# design.net
KiCad netlist of a schematic drawn in EasyEDA Pro
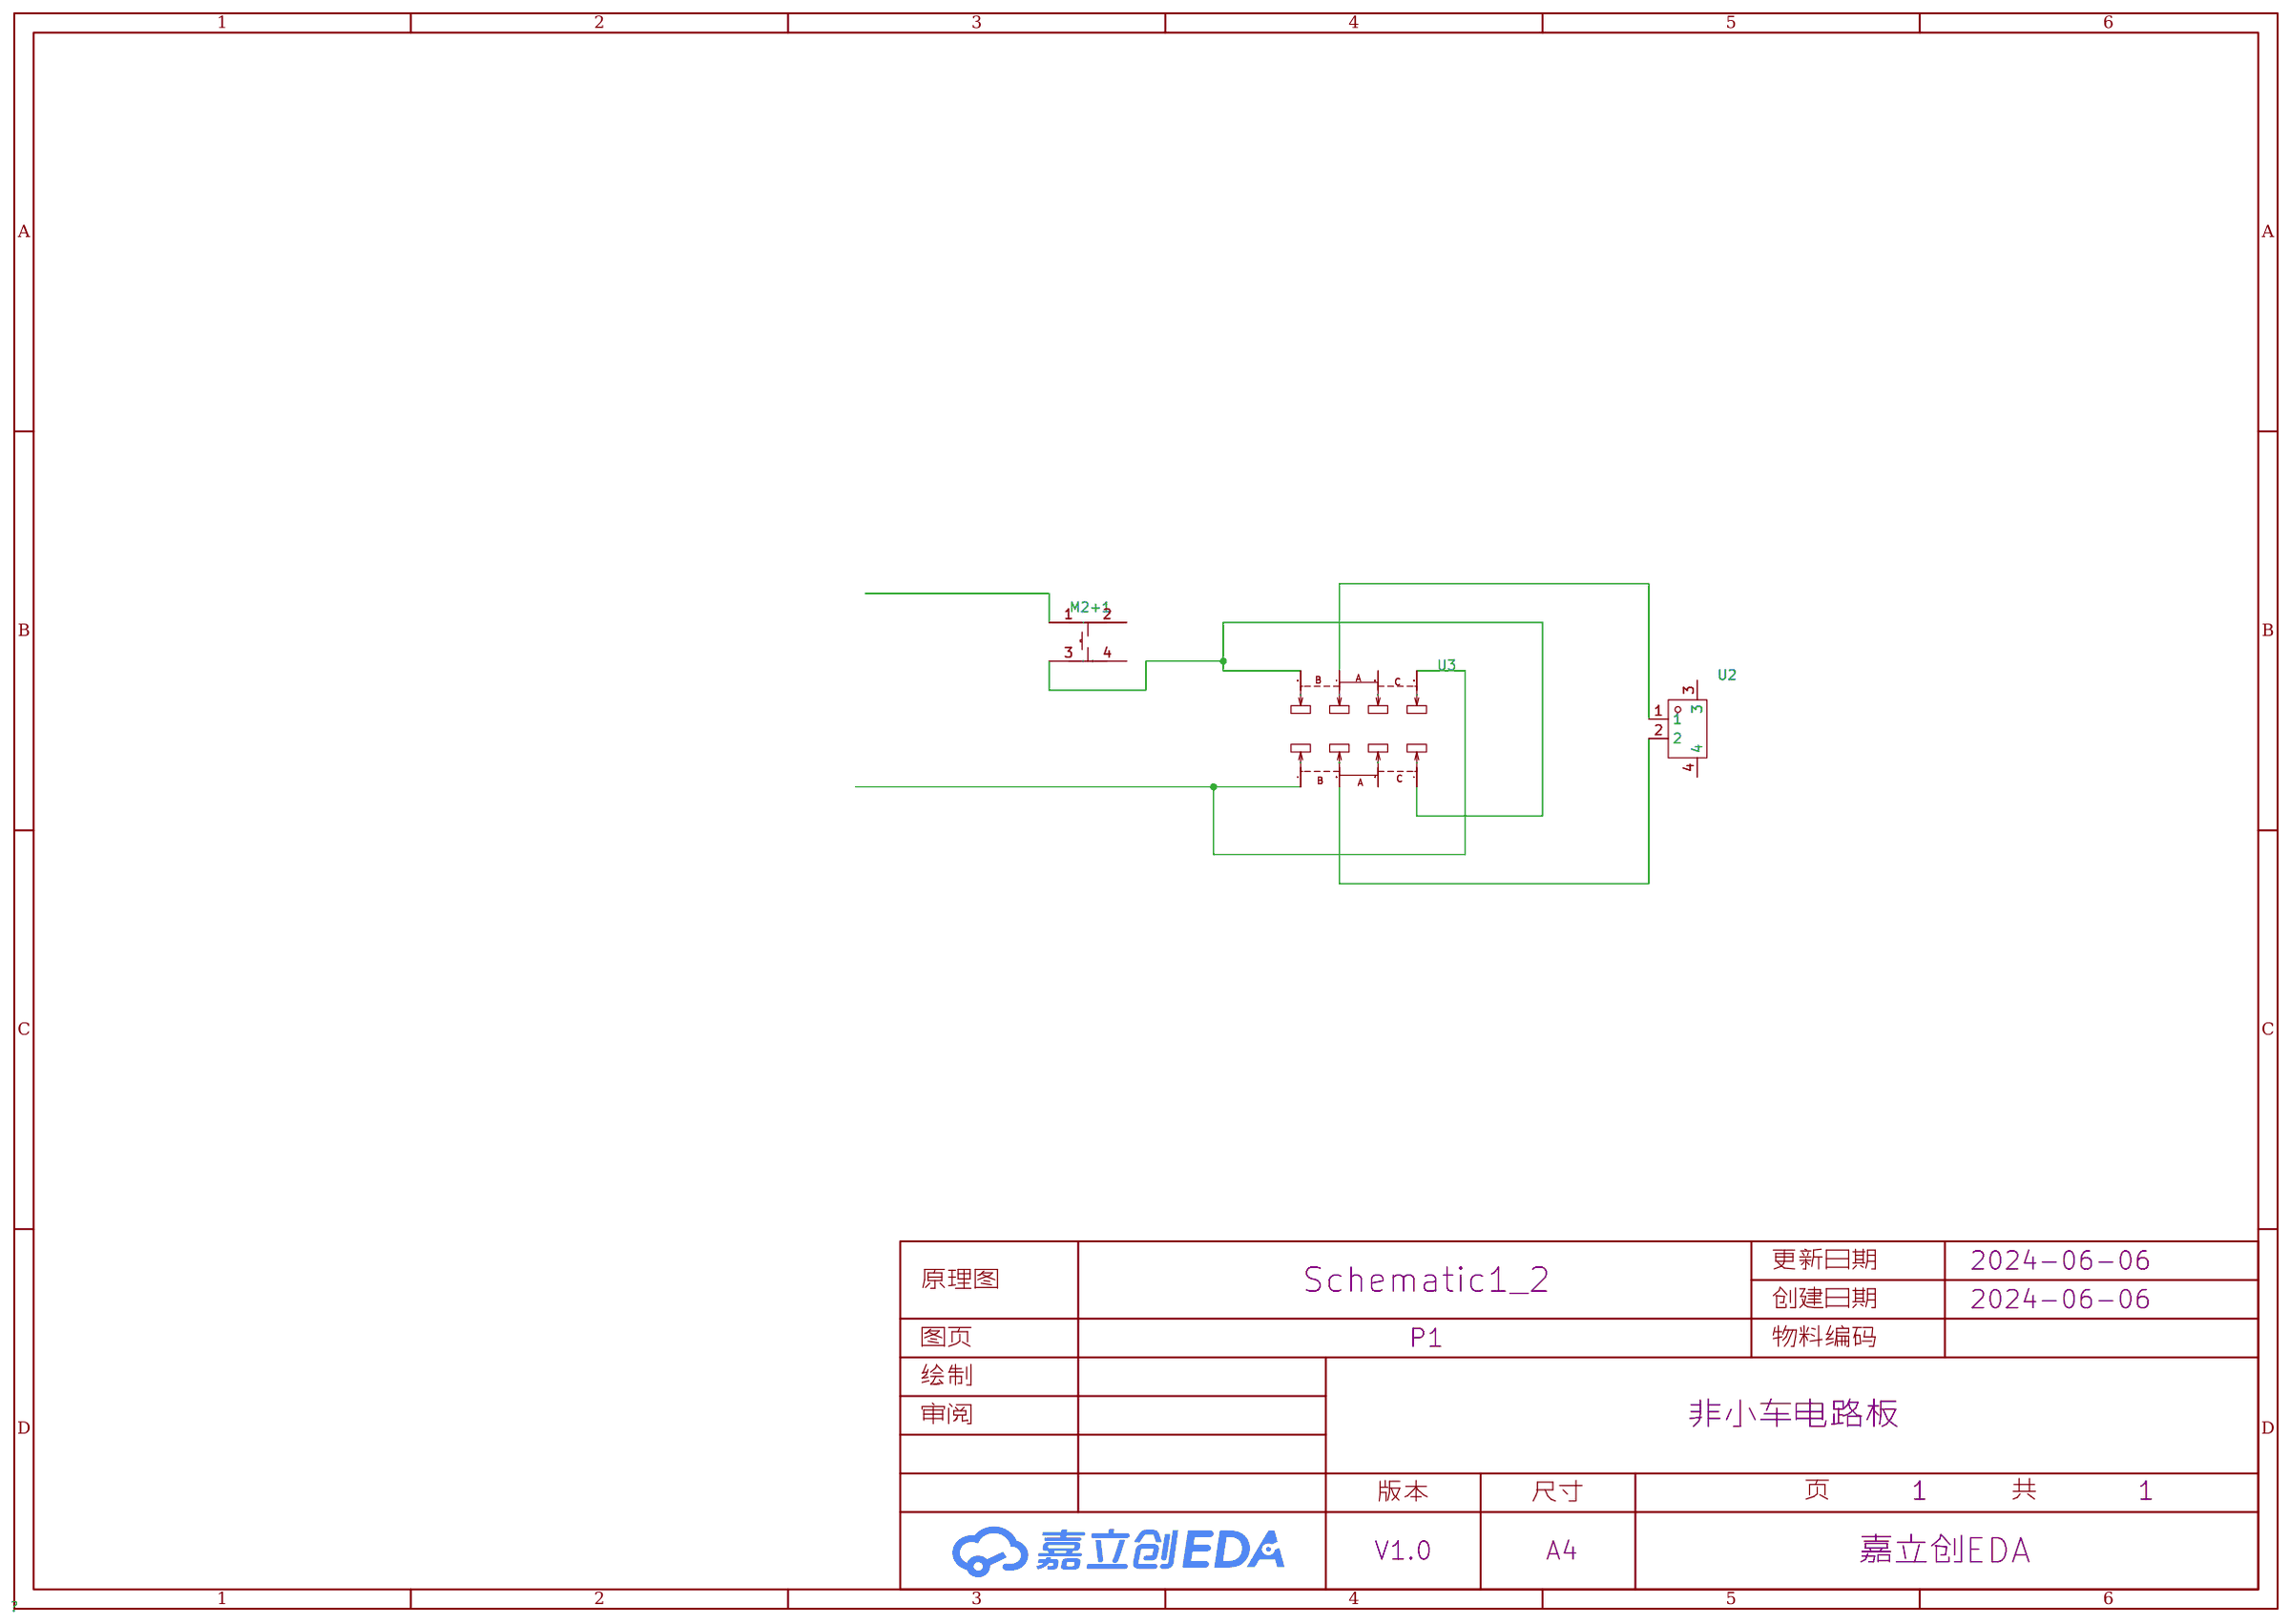
[diagram p0: schematic sheet]

(export (version "E")
  (design (tool "Eeschema 10.0.6"))
  (components
    (comp (ref "M2+1")
      (value "TS-1095S-A1B3-C2D1")
      (footprint "easyedapro:SW-SMD_4P-L6.0-W6.0-P4.50-LS8.5")
      (description "电路结构:单刀单掷;按钮作用方向:顶部触动;致动器样式:圆形按钮;照明颜色:-;作用力:250gf ±30gf;开关长度:6mm;开关宽度:6mm;开关高度:4.3mm;")
      (fields (field (name "Manufacturer") "Yuandi(元迪)"))
      (libsource (lib "easyedapro") (part "TS-1095S-A1B3-C2D1"))
    )
    (comp (ref "U2")
      (value "XD-GH-2PWT")
      (footprint "easyedapro:CONN-SMD_GH-2PWT")
      (description "参考系列:GH;间距:1.25mm;插针结构:1x2P;排数:1;每排PIN数:2;公母:公型插针;安装方式:卧贴;额定电流:1A;触头镀层:锡;工作温度范围:-40°C~+105°C;")
      (fields (field (name "Manufacturer") "XUNDA(讯答)"))
      (libsource (lib "easyedapro") (part "XD-GH-2PWT"))
    )
    (comp (ref "U3")
      (value "HX MST23D18G2")
      (footprint "easyedapro:SW-SMD_SHOU_MST23D18G2")
      (description "开关长度:13mm;开关宽度:3.5mm;开关高度:3mm;机械寿命:-;")
      (fields (field (name "Manufacturer") "hanxia(韩下)"))
      (libsource (lib "easyedapro") (part "HX MST23D18G2"))
    )
  )
  (nets
    (net (code "1") (name "Net-(M2+1-Pad3)") (class "Default")
      (node (ref "M2+1") (pin "3") (pinfunction "3_3") (pintype "input"))
      (node (ref "U3") (pin "4") (pinfunction "4_4") (pintype "unspecified"))
      (node (ref "U3") (pin "8") (pinfunction "8_8") (pintype "unspecified"))
    )
    (net (code "2") (name "Net-(U2-Pad1)") (class "Default")
      (node (ref "U2") (pin "1") (pinfunction "1_1") (pintype "unspecified"))
      (node (ref "U3") (pin "7") (pinfunction "7_7") (pintype "unspecified"))
    )
    (net (code "3") (name "Net-(U2-Pad2)") (class "Default")
      (node (ref "U2") (pin "2") (pinfunction "2_2") (pintype "unspecified"))
      (node (ref "U3") (pin "2") (pinfunction "2_2") (pintype "unspecified"))
    )
    (net (code "4") (name "Net-(U3-Pad1)") (class "Default")
      (node (ref "U3") (pin "1") (pinfunction "1_1") (pintype "unspecified"))
      (node (ref "U3") (pin "5") (pinfunction "5_5") (pintype "unspecified"))
    )
    (net (code "5") (name "unconnected-(M2+1-Pad1)") (class "Default")
      (node (ref "M2+1") (pin "1") (pinfunction "1_1") (pintype "input"))
    )
    (net (code "6") (name "unconnected-(M2+1-Pad2)") (class "Default")
      (node (ref "M2+1") (pin "2") (pinfunction "2_2") (pintype "input"))
    )
    (net (code "7") (name "unconnected-(M2+1-Pad4)") (class "Default")
      (node (ref "M2+1") (pin "4") (pinfunction "4_4") (pintype "input"))
    )
    (net (code "8") (name "unconnected-(U2-Pad3)") (class "Default")
      (node (ref "U2") (pin "3") (pinfunction "3_3") (pintype "unspecified"))
    )
    (net (code "9") (name "unconnected-(U2-Pad4)") (class "Default")
      (node (ref "U2") (pin "4") (pinfunction "4_4") (pintype "unspecified"))
    )
    (net (code "10") (name "unconnected-(U3-Pad3)") (class "Default")
      (node (ref "U3") (pin "3") (pinfunction "3_3") (pintype "unspecified"))
    )
    (net (code "11") (name "unconnected-(U3-Pad6)") (class "Default")
      (node (ref "U3") (pin "6") (pinfunction "6_6") (pintype "unspecified"))
    )
  )
)
